# 12_Supply.net
KiCad netlist of a schematic drawn in Altium Designer
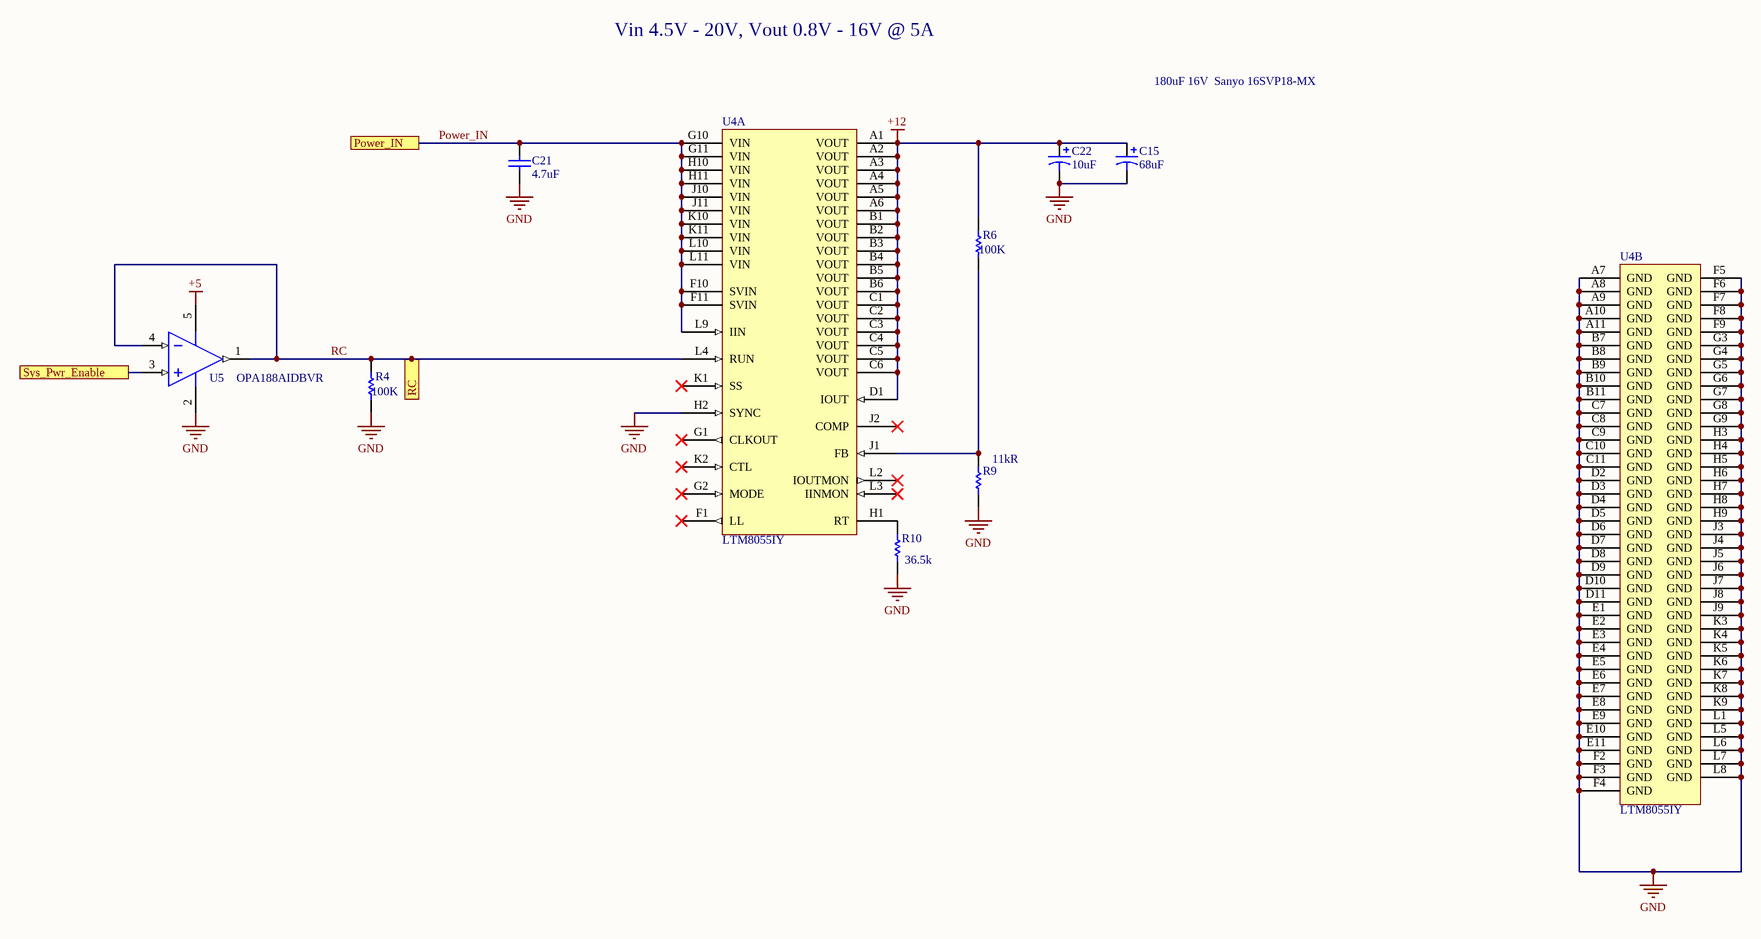
[diagram p0: 12_Supply.SchDoc]

(export (version "E")
  (design (tool "Eeschema 10.0.6"))
  (components
    (comp (ref "C15")
      (value "68uF")
      (footprint "AVX-CAPC7343_V")
      (description "CAP TANT POLY 68UF 25V 2917")
      (fields
        (field (name "MANUFACTURER") "Kyocera AVX")
        (field (name "MANUFACTURER PART NUMBER") "TCJE686M025R0050")
      )
      (libsource (lib "Altium Content Vault") (part "AVX-CAP-P-2"))
    )
    (comp (ref "C21")
      (value "4.7uF")
      (footprint "CAPC1210(3225)100_M")
      (description "CAP CER 4.7UF 50V X7R 1210")
      (fields
        (field (name "MANUFACTURER") "Murata")
        (field (name "MANUFACTURER PART NUMBER") "GCM32ER71H475KA55K")
      )
      (libsource (lib "Altium Content Vault") (part "CAP"))
    )
    (comp (ref "C22")
      (value "10uF")
      (footprint "C0805")
      (description "Polarized Capacitor (Surface Mount)")
      (libsource (lib "Miscellaneous Devices") (part "Cap Pol3"))
    )
    (comp (ref "R4")
      (value "RES SMD 100K OHM 1% 1/8W 0805")
      (footprint "RESC0805(2012)_M")
      (fields
        (field (name "MANUFACTURER") "Vishay")
        (field (name "MANUFACTURER PART NUMBER") "CRCW0805100KFKEA")
        (field (name "TOLERANCE") "1%")
        (field (name "RESISTANCE") "100K")
      )
      (libsource (lib "Altium Content Vault") (part "CMP-1013-00017-1"))
    )
    (comp (ref "R6")
      (value "RES SMD 100K OHM 1% 1/8W 0805")
      (footprint "RESC0805(2012)_M")
      (fields
        (field (name "MANUFACTURER") "Vishay")
        (field (name "MANUFACTURER PART NUMBER") "CRCW0805100KFKEA")
        (field (name "TOLERANCE") "1%")
        (field (name "RESISTANCE") "100K")
      )
      (libsource (lib "Altium Content Vault") (part "CMP-1013-00017-1"))
    )
    (comp (ref "R9")
      (value "RES SMD 11K OHM 1% 1/8W 0805")
      (footprint "RESC0805(2012)_M")
      (fields
        (field (name "MANUFACTURER") "TE Connectivity Holsworthy")
        (field (name "MANUFACTURER PART NUMBER") "CRG0805F11K")
        (field (name "RESISTANCE") "11kR")
        (field (name "TOLERANCE") "1%")
      )
      (libsource (lib "Altium Content Vault") (part "CMP-1013-00017-1"))
    )
    (comp (ref "R10")
      (value "RES SMD 35K OHM 1% 1/8W 0805")
      (footprint "RESC0805(2012)_M")
      (fields
        (field (name "MANUFACTURER") "Vishay")
        (field (name "MANUFACTURER PART NUMBER") "CRCW080536K5FKEA")
        (field (name "TOLERANCE") "1%")
        (field (name "RESISTANCE") "36.5k")
      )
      (libsource (lib "Altium Content Vault") (part "CMP-1013-00017-1"))
    )
    (comp (ref "U4")
      (value "LTM8055IY")
      (footprint "LT-BGA-121-15000X15000X4920")
      (description "Buck-Boost uModule Regulator, 8.5 A, 5 to 36 V, -40 to 125 degC, 121-Ball BGA, RoHS, Tray")
      (fields (field (name "MANUFACTURER") "LinearTechnology"))
      (libsource (lib "Altium Content Vault") (part "LT-LTM8055-BGA-121"))
    )
    (comp (ref "U5")
      (value "OPA188AIDBVR")
      (footprint "DBV0005A_M")
      (fields (field (name "MANUFACTURER") "Texas Instruments"))
      (libsource (lib "Altium Content Vault") (part "CMP-0809-00005-2"))
    )
  )
  (nets
    (net (code "1") (name "+5") (class "Default")
      (node (ref "U5") (pin "5") (pinfunction "V+_5") (pintype "power_in"))
    )
    (net (code "2") (name "+12") (class "Default")
      (node (ref "C15") (pin "1") (pinfunction "1_1") (pintype "passive"))
      (node (ref "C22") (pin "1") (pinfunction "1_1") (pintype "passive"))
      (node (ref "R6") (pin "1") (pinfunction "1_1") (pintype "passive"))
      (node (ref "U4") (pin "A1") (pinfunction "VOUT_A1") (pintype "power_in"))
      (node (ref "U4") (pin "A2") (pinfunction "VOUT_A2") (pintype "power_in"))
      (node (ref "U4") (pin "A3") (pinfunction "VOUT_A3") (pintype "power_in"))
      (node (ref "U4") (pin "A4") (pinfunction "VOUT_A4") (pintype "power_in"))
      (node (ref "U4") (pin "A5") (pinfunction "VOUT_A5") (pintype "power_in"))
      (node (ref "U4") (pin "A6") (pinfunction "VOUT_A6") (pintype "power_in"))
      (node (ref "U4") (pin "B1") (pinfunction "VOUT_B1") (pintype "power_in"))
      (node (ref "U4") (pin "B2") (pinfunction "VOUT_B2") (pintype "power_in"))
      (node (ref "U4") (pin "B3") (pinfunction "VOUT_B3") (pintype "power_in"))
      (node (ref "U4") (pin "B4") (pinfunction "VOUT_B4") (pintype "power_in"))
      (node (ref "U4") (pin "B5") (pinfunction "VOUT_B5") (pintype "power_in"))
      (node (ref "U4") (pin "B6") (pinfunction "VOUT_B6") (pintype "power_in"))
      (node (ref "U4") (pin "C1") (pinfunction "VOUT_C1") (pintype "power_in"))
      (node (ref "U4") (pin "C2") (pinfunction "VOUT_C2") (pintype "power_in"))
      (node (ref "U4") (pin "C3") (pinfunction "VOUT_C3") (pintype "power_in"))
      (node (ref "U4") (pin "C4") (pinfunction "VOUT_C4") (pintype "power_in"))
      (node (ref "U4") (pin "C5") (pinfunction "VOUT_C5") (pintype "power_in"))
      (node (ref "U4") (pin "C6") (pinfunction "VOUT_C6") (pintype "power_in"))
      (node (ref "U4") (pin "D1") (pinfunction "IOUT_D1") (pintype "input"))
    )
    (net (code "3") (name "/Power_IN") (class "Default")
      (node (ref "C21") (pin "2") (pinfunction "2_2") (pintype "passive"))
      (node (ref "U4") (pin "F10") (pinfunction "SVIN_F10") (pintype "power_in"))
      (node (ref "U4") (pin "F11") (pinfunction "SVIN_F11") (pintype "power_in"))
      (node (ref "U4") (pin "G10") (pinfunction "VIN_G10") (pintype "power_in"))
      (node (ref "U4") (pin "G11") (pinfunction "VIN_G11") (pintype "power_in"))
      (node (ref "U4") (pin "H10") (pinfunction "VIN_H10") (pintype "power_in"))
      (node (ref "U4") (pin "H11") (pinfunction "VIN_H11") (pintype "power_in"))
      (node (ref "U4") (pin "J10") (pinfunction "VIN_J10") (pintype "power_in"))
      (node (ref "U4") (pin "J11") (pinfunction "VIN_J11") (pintype "power_in"))
      (node (ref "U4") (pin "K10") (pinfunction "VIN_K10") (pintype "power_in"))
      (node (ref "U4") (pin "K11") (pinfunction "VIN_K11") (pintype "power_in"))
      (node (ref "U4") (pin "L10") (pinfunction "VIN_L10") (pintype "power_in"))
      (node (ref "U4") (pin "L11") (pinfunction "VIN_L11") (pintype "power_in"))
      (node (ref "U4") (pin "L9") (pinfunction "IIN_L9") (pintype "input"))
    )
    (net (code "4") (name "/RC") (class "Default")
      (node (ref "R4") (pin "1") (pinfunction "1_1") (pintype "passive"))
      (node (ref "U4") (pin "L4") (pinfunction "RUN_L4") (pintype "input"))
      (node (ref "U5") (pin "1") (pinfunction "OUT_1") (pintype "output"))
      (node (ref "U5") (pin "4") (pinfunction "IN-_4") (pintype "input"))
    )
    (net (code "5") (name "/Sys_Pwr_Enable") (class "Default")
      (node (ref "U5") (pin "3") (pinfunction "IN+_3") (pintype "input"))
    )
    (net (code "6") (name "GND") (class "Default")
      (node (ref "C15") (pin "2") (pinfunction "2_2") (pintype "passive"))
      (node (ref "C21") (pin "1") (pinfunction "1_1") (pintype "passive"))
      (node (ref "C22") (pin "2") (pinfunction "2_2") (pintype "passive"))
      (node (ref "R10") (pin "2") (pinfunction "2_2") (pintype "passive"))
      (node (ref "R4") (pin "2") (pinfunction "2_2") (pintype "passive"))
      (node (ref "R9") (pin "2") (pinfunction "2_2") (pintype "passive"))
      (node (ref "U4") (pin "A10") (pinfunction "GND_A10") (pintype "power_in"))
      (node (ref "U4") (pin "A11") (pinfunction "GND_A11") (pintype "power_in"))
      (node (ref "U4") (pin "A7") (pinfunction "GND_A7") (pintype "power_in"))
      (node (ref "U4") (pin "A8") (pinfunction "GND_A8") (pintype "power_in"))
      (node (ref "U4") (pin "A9") (pinfunction "GND_A9") (pintype "power_in"))
      (node (ref "U4") (pin "B10") (pinfunction "GND_B10") (pintype "power_in"))
      (node (ref "U4") (pin "B11") (pinfunction "GND_B11") (pintype "power_in"))
      (node (ref "U4") (pin "B7") (pinfunction "GND_B7") (pintype "power_in"))
      (node (ref "U4") (pin "B8") (pinfunction "GND_B8") (pintype "power_in"))
      (node (ref "U4") (pin "B9") (pinfunction "GND_B9") (pintype "power_in"))
      (node (ref "U4") (pin "C10") (pinfunction "GND_C10") (pintype "power_in"))
      (node (ref "U4") (pin "C11") (pinfunction "GND_C11") (pintype "power_in"))
      (node (ref "U4") (pin "C7") (pinfunction "GND_C7") (pintype "power_in"))
      (node (ref "U4") (pin "C8") (pinfunction "GND_C8") (pintype "power_in"))
      (node (ref "U4") (pin "C9") (pinfunction "GND_C9") (pintype "power_in"))
      (node (ref "U4") (pin "D10") (pinfunction "GND_D10") (pintype "power_in"))
      (node (ref "U4") (pin "D11") (pinfunction "GND_D11") (pintype "power_in"))
      (node (ref "U4") (pin "D2") (pinfunction "GND_D2") (pintype "power_in"))
      (node (ref "U4") (pin "D3") (pinfunction "GND_D3") (pintype "power_in"))
      (node (ref "U4") (pin "D4") (pinfunction "GND_D4") (pintype "power_in"))
      (node (ref "U4") (pin "D5") (pinfunction "GND_D5") (pintype "power_in"))
      (node (ref "U4") (pin "D6") (pinfunction "GND_D6") (pintype "power_in"))
      (node (ref "U4") (pin "D7") (pinfunction "GND_D7") (pintype "power_in"))
      (node (ref "U4") (pin "D8") (pinfunction "GND_D8") (pintype "power_in"))
      (node (ref "U4") (pin "D9") (pinfunction "GND_D9") (pintype "power_in"))
      (node (ref "U4") (pin "E1") (pinfunction "GND_E1") (pintype "power_in"))
      (node (ref "U4") (pin "E10") (pinfunction "GND_E10") (pintype "power_in"))
      (node (ref "U4") (pin "E11") (pinfunction "GND_E11") (pintype "power_in"))
      (node (ref "U4") (pin "E2") (pinfunction "GND_E2") (pintype "power_in"))
      (node (ref "U4") (pin "E3") (pinfunction "GND_E3") (pintype "power_in"))
      (node (ref "U4") (pin "E4") (pinfunction "GND_E4") (pintype "power_in"))
      (node (ref "U4") (pin "E5") (pinfunction "GND_E5") (pintype "power_in"))
      (node (ref "U4") (pin "E6") (pinfunction "GND_E6") (pintype "power_in"))
      (node (ref "U4") (pin "E7") (pinfunction "GND_E7") (pintype "power_in"))
      (node (ref "U4") (pin "E8") (pinfunction "GND_E8") (pintype "power_in"))
      (node (ref "U4") (pin "E9") (pinfunction "GND_E9") (pintype "power_in"))
      (node (ref "U4") (pin "F2") (pinfunction "GND_F2") (pintype "power_in"))
      (node (ref "U4") (pin "F3") (pinfunction "GND_F3") (pintype "power_in"))
      (node (ref "U4") (pin "F4") (pinfunction "GND_F4") (pintype "power_in"))
      (node (ref "U4") (pin "F5") (pinfunction "GND_F5") (pintype "power_in"))
      (node (ref "U4") (pin "F6") (pinfunction "GND_F6") (pintype "power_in"))
      (node (ref "U4") (pin "F7") (pinfunction "GND_F7") (pintype "power_in"))
      (node (ref "U4") (pin "F8") (pinfunction "GND_F8") (pintype "power_in"))
      (node (ref "U4") (pin "F9") (pinfunction "GND_F9") (pintype "power_in"))
      (node (ref "U4") (pin "G3") (pinfunction "GND_G3") (pintype "power_in"))
      (node (ref "U4") (pin "G4") (pinfunction "GND_G4") (pintype "power_in"))
      (node (ref "U4") (pin "G5") (pinfunction "GND_G5") (pintype "power_in"))
      (node (ref "U4") (pin "G6") (pinfunction "GND_G6") (pintype "power_in"))
      (node (ref "U4") (pin "G7") (pinfunction "GND_G7") (pintype "power_in"))
      (node (ref "U4") (pin "G8") (pinfunction "GND_G8") (pintype "power_in"))
      (node (ref "U4") (pin "G9") (pinfunction "GND_G9") (pintype "power_in"))
      (node (ref "U4") (pin "H2") (pinfunction "SYNC_H2") (pintype "input"))
      (node (ref "U4") (pin "H3") (pinfunction "GND_H3") (pintype "power_in"))
      (node (ref "U4") (pin "H4") (pinfunction "GND_H4") (pintype "power_in"))
      (node (ref "U4") (pin "H5") (pinfunction "GND_H5") (pintype "power_in"))
      (node (ref "U4") (pin "H6") (pinfunction "GND_H6") (pintype "power_in"))
      (node (ref "U4") (pin "H7") (pinfunction "GND_H7") (pintype "power_in"))
      (node (ref "U4") (pin "H8") (pinfunction "GND_H8") (pintype "power_in"))
      (node (ref "U4") (pin "H9") (pinfunction "GND_H9") (pintype "power_in"))
      (node (ref "U4") (pin "J3") (pinfunction "GND_J3") (pintype "power_in"))
      (node (ref "U4") (pin "J4") (pinfunction "GND_J4") (pintype "power_in"))
      (node (ref "U4") (pin "J5") (pinfunction "GND_J5") (pintype "power_in"))
      (node (ref "U4") (pin "J6") (pinfunction "GND_J6") (pintype "power_in"))
      (node (ref "U4") (pin "J7") (pinfunction "GND_J7") (pintype "power_in"))
      (node (ref "U4") (pin "J8") (pinfunction "GND_J8") (pintype "power_in"))
      (node (ref "U4") (pin "J9") (pinfunction "GND_J9") (pintype "power_in"))
      (node (ref "U4") (pin "K3") (pinfunction "GND_K3") (pintype "power_in"))
      (node (ref "U4") (pin "K4") (pinfunction "GND_K4") (pintype "power_in"))
      (node (ref "U4") (pin "K5") (pinfunction "GND_K5") (pintype "power_in"))
      (node (ref "U4") (pin "K6") (pinfunction "GND_K6") (pintype "power_in"))
      (node (ref "U4") (pin "K7") (pinfunction "GND_K7") (pintype "power_in"))
      (node (ref "U4") (pin "K8") (pinfunction "GND_K8") (pintype "power_in"))
      (node (ref "U4") (pin "K9") (pinfunction "GND_K9") (pintype "power_in"))
      (node (ref "U4") (pin "L1") (pinfunction "GND_L1") (pintype "power_in"))
      (node (ref "U4") (pin "L5") (pinfunction "GND_L5") (pintype "power_in"))
      (node (ref "U4") (pin "L6") (pinfunction "GND_L6") (pintype "power_in"))
      (node (ref "U4") (pin "L7") (pinfunction "GND_L7") (pintype "power_in"))
      (node (ref "U4") (pin "L8") (pinfunction "GND_L8") (pintype "power_in"))
      (node (ref "U5") (pin "2") (pinfunction "V-_2") (pintype "power_in"))
    )
    (net (code "7") (name "Net-(U4A-FB)") (class "Default")
      (node (ref "R6") (pin "2") (pinfunction "2_2") (pintype "passive"))
      (node (ref "R9") (pin "1") (pinfunction "1_1") (pintype "passive"))
      (node (ref "U4") (pin "J1") (pinfunction "FB_J1") (pintype "input"))
    )
    (net (code "8") (name "Net-(U4A-RT)") (class "Default")
      (node (ref "R10") (pin "1") (pinfunction "1_1") (pintype "passive"))
      (node (ref "U4") (pin "H1") (pinfunction "RT_H1") (pintype "passive"))
    )
    (net (code "9") (name "unconnected-(U4A-CLKOUT-PadG1)") (class "Default")
      (node (ref "U4") (pin "G1") (pinfunction "CLKOUT_G1") (pintype "output+no_connect"))
    )
    (net (code "10") (name "unconnected-(U4A-COMP-PadJ2)") (class "Default")
      (node (ref "U4") (pin "J2") (pinfunction "COMP_J2") (pintype "passive+no_connect"))
    )
    (net (code "11") (name "unconnected-(U4A-CTL-PadK2)") (class "Default")
      (node (ref "U4") (pin "K2") (pinfunction "CTL_K2") (pintype "input+no_connect"))
    )
    (net (code "12") (name "unconnected-(U4A-IINMON-PadL3)") (class "Default")
      (node (ref "U4") (pin "L3") (pinfunction "IINMON_L3") (pintype "input+no_connect"))
    )
    (net (code "13") (name "unconnected-(U4A-IOUTMON-PadL2)") (class "Default")
      (node (ref "U4") (pin "L2") (pinfunction "IOUTMON_L2") (pintype "output+no_connect"))
    )
    (net (code "14") (name "unconnected-(U4A-LL-PadF1)") (class "Default")
      (node (ref "U4") (pin "F1") (pinfunction "LL_F1") (pintype "output+no_connect"))
    )
    (net (code "15") (name "unconnected-(U4A-MODE-PadG2)") (class "Default")
      (node (ref "U4") (pin "G2") (pinfunction "MODE_G2") (pintype "input+no_connect"))
    )
    (net (code "16") (name "unconnected-(U4A-SS-PadK1)") (class "Default")
      (node (ref "U4") (pin "K1") (pinfunction "SS_K1") (pintype "input+no_connect"))
    )
  )
)
